# TMC2130.net
KiCad netlist of a schematic drawn in Altium Designer
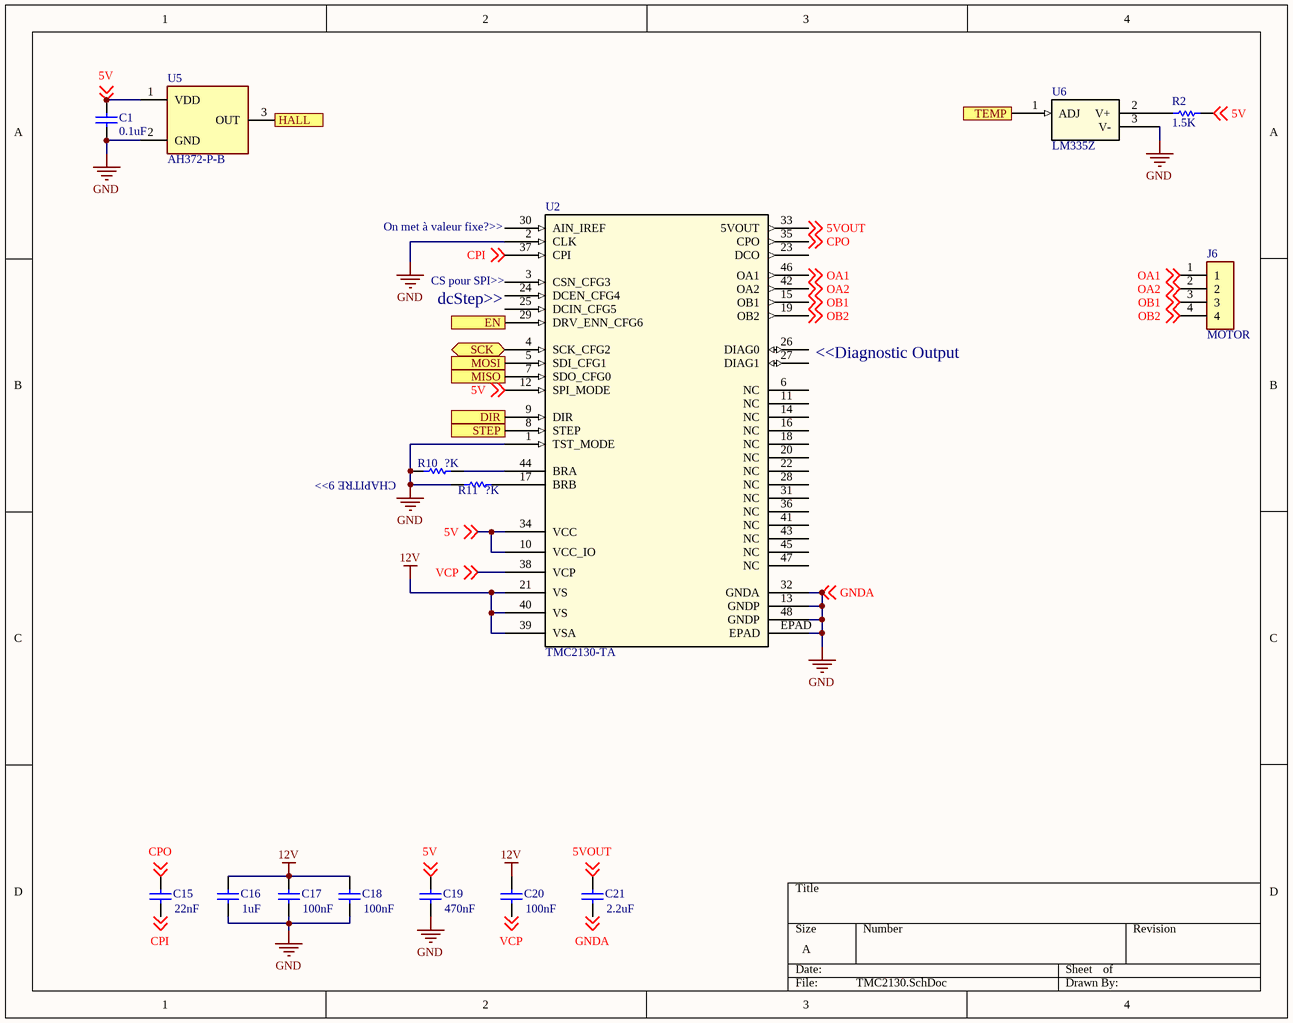
[diagram p0: TMC2130.SchDoc]

(export (version "E")
  (design (tool "Eeschema 10.0.6"))
  (components
    (comp (ref "C1")
      (value "0.1uF")
      (footprint "RAD-0.3")
      (description "Capacitor")
      (fields (field (name "PUBLISHER") "Altium Limited"))
      (libsource (lib "Miscellaneous Devices") (part "Cap"))
    )
    (comp (ref "C15")
      (value "22nF")
      (footprint "RAD-0.3")
      (description "Capacitor")
      (fields (field (name "Comment") "Cap") (field (name "PUBLISHER") "Altium Limited"))
      (libsource (lib "Miscellaneous Devices") (part "Cap"))
    )
    (comp (ref "C16")
      (value "1uF")
      (footprint "RAD-0.3")
      (description "Capacitor")
      (fields (field (name "Comment") "Cap") (field (name "PUBLISHER") "Altium Limited"))
      (libsource (lib "Miscellaneous Devices") (part "Cap"))
    )
    (comp (ref "C17")
      (value "100nF")
      (footprint "RAD-0.3")
      (description "Capacitor")
      (fields (field (name "Comment") "Cap") (field (name "PUBLISHER") "Altium Limited"))
      (libsource (lib "Miscellaneous Devices") (part "Cap"))
    )
    (comp (ref "C18")
      (value "100nF")
      (footprint "RAD-0.3")
      (description "Capacitor")
      (fields (field (name "Comment") "Cap") (field (name "PUBLISHER") "Altium Limited"))
      (libsource (lib "Miscellaneous Devices") (part "Cap"))
    )
    (comp (ref "C19")
      (value "470nF")
      (footprint "RAD-0.3")
      (description "Capacitor")
      (fields (field (name "Comment") "Cap") (field (name "PUBLISHER") "Altium Limited"))
      (libsource (lib "Miscellaneous Devices") (part "Cap"))
    )
    (comp (ref "C20")
      (value "100nF")
      (footprint "RAD-0.3")
      (description "Capacitor")
      (fields (field (name "Comment") "Cap") (field (name "PUBLISHER") "Altium Limited"))
      (libsource (lib "Miscellaneous Devices") (part "Cap"))
    )
    (comp (ref "C21")
      (value "2.2uF")
      (footprint "RAD-0.3")
      (description "Capacitor")
      (fields (field (name "Comment") "Cap") (field (name "PUBLISHER") "Altium Limited"))
      (libsource (lib "Miscellaneous Devices") (part "Cap"))
    )
    (comp (ref "J6")
      (value "MOTOR")
      (footprint "Footprint_Emile:SHDR4W64P0X250_1X4_1240X1155X700P")
      (description "Connector")
      (fields
        (field (name "MANUFACTURER_PART_NUMBER") "S4B-XH-A(LF)(SN)")
        (field (name "RS PART NUMBER") "8201589P")
      )
      (libsource (lib "Schematic_Emile") (part "JST 4POS"))
    )
    (comp (ref "R2")
      (value "1.5K")
      (footprint "AXIAL-0.3")
      (description "Resistor")
      (fields (field (name "PUBLISHER") "Altium Limited"))
      (libsource (lib "Miscellaneous Devices") (part "Res1"))
    )
    (comp (ref "R10")
      (value "?K")
      (footprint "AXIAL-0.3")
      (description "Resistor")
      (fields (field (name "Comment") "Res1") (field (name "PUBLISHER") "Altium Limited"))
      (libsource (lib "Miscellaneous Devices") (part "Res1"))
    )
    (comp (ref "R11")
      (value "?K")
      (footprint "AXIAL-0.3")
      (description "Resistor")
      (fields (field (name "Comment") "Res1") (field (name "PUBLISHER") "Altium Limited"))
      (libsource (lib "Miscellaneous Devices") (part "Res1"))
    )
    (comp (ref "U2")
      (value "TMC2130-TA")
      (footprint "eTQFP48_9x9")
      (description "Motor Driver TMC2130")
      (fields (field (name "COPYRIGHT") "Copyright (C) 2016 Accelerated Designs. All rights reserved"))
      (libsource (lib "Schematic_Emile") (part "TMC2130-TA"))
    )
    (comp (ref "U5")
      (value "AH372-P-B")
      (footprint "SamacSys:AH372PB")
      (description "Hall Sensor")
      (fields (field (name "MOUSER PART NUMBER") "621-AH372-P-B") (field (name "RS PART NUMBER") "1333361P"))
      (libsource (lib "Schematic_Emile") (part "AH372-P-B"))
    )
    (comp (ref "U6")
      (value "LM335Z")
      (footprint "TO92")
      (description "Temperature Sensor")
      (fields (field (name "COPYRIGHT") "Copyright (C) 2018 Accelerated Designs. All rights reserved"))
      (libsource (lib "Schematic_Emile") (part "LM335Z"))
    )
  )
  (nets
    (net (code "1") (name "/DIR") (class "Default")
      (node (ref "U2") (pin "9") (pinfunction "DIR_9") (pintype "input"))
    )
    (net (code "2") (name "/EN") (class "Default")
      (node (ref "U2") (pin "29") (pinfunction "DRV_ENN_CFG6_29") (pintype "input"))
    )
    (net (code "3") (name "/HALL") (class "Default")
      (node (ref "U5") (pin "3") (pinfunction "OUT_3") (pintype "passive"))
    )
    (net (code "4") (name "/MISO") (class "Default")
      (node (ref "U2") (pin "7") (pinfunction "SDO_CFG0_7") (pintype "input"))
    )
    (net (code "5") (name "/MOSI") (class "Default")
      (node (ref "U2") (pin "5") (pinfunction "SDI_CFG1_5") (pintype "input"))
    )
    (net (code "6") (name "/SCK") (class "Default")
      (node (ref "U2") (pin "4") (pinfunction "SCK_CFG2_4") (pintype "input"))
    )
    (net (code "7") (name "/STEP") (class "Default")
      (node (ref "U2") (pin "8") (pinfunction "STEP_8") (pintype "input"))
    )
    (net (code "8") (name "/TEMP") (class "Default")
      (node (ref "U6") (pin "1") (pinfunction "ADJ_1") (pintype "input"))
    )
    (net (code "9") (name "5V") (class "Default")
      (node (ref "C1") (pin "2") (pinfunction "2_2") (pintype "passive"))
      (node (ref "C19") (pin "2") (pinfunction "2_2") (pintype "passive"))
      (node (ref "R2") (pin "1") (pinfunction "1_1") (pintype "passive"))
      (node (ref "U2") (pin "10") (pinfunction "VCC_IO_10") (pintype "power_in"))
      (node (ref "U2") (pin "12") (pinfunction "SPI_MODE_12") (pintype "input"))
      (node (ref "U2") (pin "34") (pinfunction "VCC_34") (pintype "power_in"))
      (node (ref "U5") (pin "1") (pinfunction "VDD_1") (pintype "passive"))
    )
    (net (code "10") (name "5VOUT") (class "Default")
      (node (ref "C21") (pin "2") (pinfunction "2_2") (pintype "passive"))
      (node (ref "U2") (pin "33") (pinfunction "5VOUT_33") (pintype "output"))
    )
    (net (code "11") (name "12V") (class "Default")
      (node (ref "C16") (pin "2") (pinfunction "2_2") (pintype "passive"))
      (node (ref "C17") (pin "2") (pinfunction "2_2") (pintype "passive"))
      (node (ref "C18") (pin "2") (pinfunction "2_2") (pintype "passive"))
      (node (ref "C20") (pin "2") (pinfunction "2_2") (pintype "passive"))
      (node (ref "U2") (pin "21") (pinfunction "VS_21") (pintype "power_in"))
      (node (ref "U2") (pin "39") (pinfunction "VSA_39") (pintype "power_in"))
      (node (ref "U2") (pin "40") (pinfunction "VS_40") (pintype "power_in"))
    )
    (net (code "12") (name "CPI") (class "Default")
      (node (ref "C15") (pin "1") (pinfunction "1_1") (pintype "passive"))
      (node (ref "U2") (pin "37") (pinfunction "CPI_37") (pintype "input"))
    )
    (net (code "13") (name "CPO") (class "Default")
      (node (ref "C15") (pin "2") (pinfunction "2_2") (pintype "passive"))
      (node (ref "U2") (pin "35") (pinfunction "CPO_35") (pintype "output"))
    )
    (net (code "14") (name "GND") (class "Default")
      (node (ref "C1") (pin "1") (pinfunction "1_1") (pintype "passive"))
      (node (ref "C16") (pin "1") (pinfunction "1_1") (pintype "passive"))
      (node (ref "C17") (pin "1") (pinfunction "1_1") (pintype "passive"))
      (node (ref "C18") (pin "1") (pinfunction "1_1") (pintype "passive"))
      (node (ref "C19") (pin "1") (pinfunction "1_1") (pintype "passive"))
      (node (ref "C21") (pin "1") (pinfunction "1_1") (pintype "passive"))
      (node (ref "R10") (pin "1") (pinfunction "1_1") (pintype "passive"))
      (node (ref "R11") (pin "1") (pinfunction "1_1") (pintype "passive"))
      (node (ref "U2") (pin "1") (pinfunction "TST_MODE_1") (pintype "input"))
      (node (ref "U2") (pin "13") (pinfunction "GNDP_13") (pintype "power_in"))
      (node (ref "U2") (pin "2") (pinfunction "CLK_2") (pintype "input"))
      (node (ref "U2") (pin "32") (pinfunction "GNDA_32") (pintype "power_in"))
      (node (ref "U2") (pin "48") (pinfunction "GNDP_48") (pintype "power_in"))
      (node (ref "U2") (pin "EPAD") (pinfunction "EPAD_EPAD") (pintype "passive"))
      (node (ref "U5") (pin "2") (pinfunction "GND_2") (pintype "passive"))
      (node (ref "U6") (pin "3") (pinfunction "V-_3") (pintype "power_in"))
    )
    (net (code "15") (name "Net-(U2-BRA)") (class "Default")
      (node (ref "R10") (pin "2") (pinfunction "2_2") (pintype "passive"))
      (node (ref "U2") (pin "44") (pinfunction "BRA_44") (pintype "passive"))
    )
    (net (code "16") (name "Net-(U2-BRB)") (class "Default")
      (node (ref "R11") (pin "2") (pinfunction "2_2") (pintype "passive"))
      (node (ref "U2") (pin "17") (pinfunction "BRB_17") (pintype "passive"))
    )
    (net (code "17") (name "Net-(U6-V+)") (class "Default")
      (node (ref "R2") (pin "2") (pinfunction "2_2") (pintype "passive"))
      (node (ref "U6") (pin "2") (pinfunction "V+_2") (pintype "power_in"))
    )
    (net (code "18") (name "OA1") (class "Default")
      (node (ref "J6") (pin "1") (pinfunction "1_1") (pintype "passive"))
      (node (ref "U2") (pin "46") (pinfunction "OA1_46") (pintype "output"))
    )
    (net (code "19") (name "OA2") (class "Default")
      (node (ref "J6") (pin "2") (pinfunction "2_2") (pintype "passive"))
      (node (ref "U2") (pin "42") (pinfunction "OA2_42") (pintype "output"))
    )
    (net (code "20") (name "OB1") (class "Default")
      (node (ref "J6") (pin "3") (pinfunction "3_3") (pintype "passive"))
      (node (ref "U2") (pin "15") (pinfunction "OB1_15") (pintype "output"))
    )
    (net (code "21") (name "OB2") (class "Default")
      (node (ref "J6") (pin "4") (pinfunction "4_4") (pintype "passive"))
      (node (ref "U2") (pin "19") (pinfunction "OB2_19") (pintype "output"))
    )
    (net (code "22") (name "VCP") (class "Default")
      (node (ref "C20") (pin "1") (pinfunction "1_1") (pintype "passive"))
      (node (ref "U2") (pin "38") (pinfunction "VCP_38") (pintype "power_in"))
    )
    (net (code "23") (name "unconnected-(U2-AIN_IREF-Pad30)") (class "Default")
      (node (ref "U2") (pin "30") (pinfunction "AIN_IREF_30") (pintype "input"))
    )
    (net (code "24") (name "unconnected-(U2-CSN_CFG3-Pad3)") (class "Default")
      (node (ref "U2") (pin "3") (pinfunction "CSN_CFG3_3") (pintype "input"))
    )
    (net (code "25") (name "unconnected-(U2-DCEN_CFG4-Pad24)") (class "Default")
      (node (ref "U2") (pin "24") (pinfunction "DCEN_CFG4_24") (pintype "input"))
    )
    (net (code "26") (name "unconnected-(U2-DCIN_CFG5-Pad25)") (class "Default")
      (node (ref "U2") (pin "25") (pinfunction "DCIN_CFG5_25") (pintype "input"))
    )
    (net (code "27") (name "unconnected-(U2-DCO-Pad23)") (class "Default")
      (node (ref "U2") (pin "23") (pinfunction "DCO_23") (pintype "output"))
    )
    (net (code "28") (name "unconnected-(U2-DIAG0-Pad26)") (class "Default")
      (node (ref "U2") (pin "26") (pinfunction "DIAG0_26") (pintype "bidirectional"))
    )
    (net (code "29") (name "unconnected-(U2-DIAG1-Pad27)") (class "Default")
      (node (ref "U2") (pin "27") (pinfunction "DIAG1_27") (pintype "bidirectional"))
    )
    (net (code "30") (name "unconnected-(U2-NC-Pad6)") (class "Default")
      (node (ref "U2") (pin "6") (pinfunction "NC_6") (pintype "passive"))
    )
    (net (code "31") (name "unconnected-(U2-NC-Pad11)") (class "Default")
      (node (ref "U2") (pin "11") (pinfunction "NC_11") (pintype "passive"))
    )
    (net (code "32") (name "unconnected-(U2-NC-Pad14)") (class "Default")
      (node (ref "U2") (pin "14") (pinfunction "NC_14") (pintype "passive"))
    )
    (net (code "33") (name "unconnected-(U2-NC-Pad16)") (class "Default")
      (node (ref "U2") (pin "16") (pinfunction "NC_16") (pintype "passive"))
    )
    (net (code "34") (name "unconnected-(U2-NC-Pad18)") (class "Default")
      (node (ref "U2") (pin "18") (pinfunction "NC_18") (pintype "passive"))
    )
    (net (code "35") (name "unconnected-(U2-NC-Pad20)") (class "Default")
      (node (ref "U2") (pin "20") (pinfunction "NC_20") (pintype "passive"))
    )
    (net (code "36") (name "unconnected-(U2-NC-Pad22)") (class "Default")
      (node (ref "U2") (pin "22") (pinfunction "NC_22") (pintype "passive"))
    )
    (net (code "37") (name "unconnected-(U2-NC-Pad28)") (class "Default")
      (node (ref "U2") (pin "28") (pinfunction "NC_28") (pintype "passive"))
    )
    (net (code "38") (name "unconnected-(U2-NC-Pad31)") (class "Default")
      (node (ref "U2") (pin "31") (pinfunction "NC_31") (pintype "passive"))
    )
    (net (code "39") (name "unconnected-(U2-NC-Pad36)") (class "Default")
      (node (ref "U2") (pin "36") (pinfunction "NC_36") (pintype "passive"))
    )
    (net (code "40") (name "unconnected-(U2-NC-Pad41)") (class "Default")
      (node (ref "U2") (pin "41") (pinfunction "NC_41") (pintype "passive"))
    )
    (net (code "41") (name "unconnected-(U2-NC-Pad43)") (class "Default")
      (node (ref "U2") (pin "43") (pinfunction "NC_43") (pintype "passive"))
    )
    (net (code "42") (name "unconnected-(U2-NC-Pad45)") (class "Default")
      (node (ref "U2") (pin "45") (pinfunction "NC_45") (pintype "passive"))
    )
    (net (code "43") (name "unconnected-(U2-NC-Pad47)") (class "Default")
      (node (ref "U2") (pin "47") (pinfunction "NC_47") (pintype "passive"))
    )
  )
)
